# HA_Out.net
KiCad netlist of a schematic drawn in Altium Designer
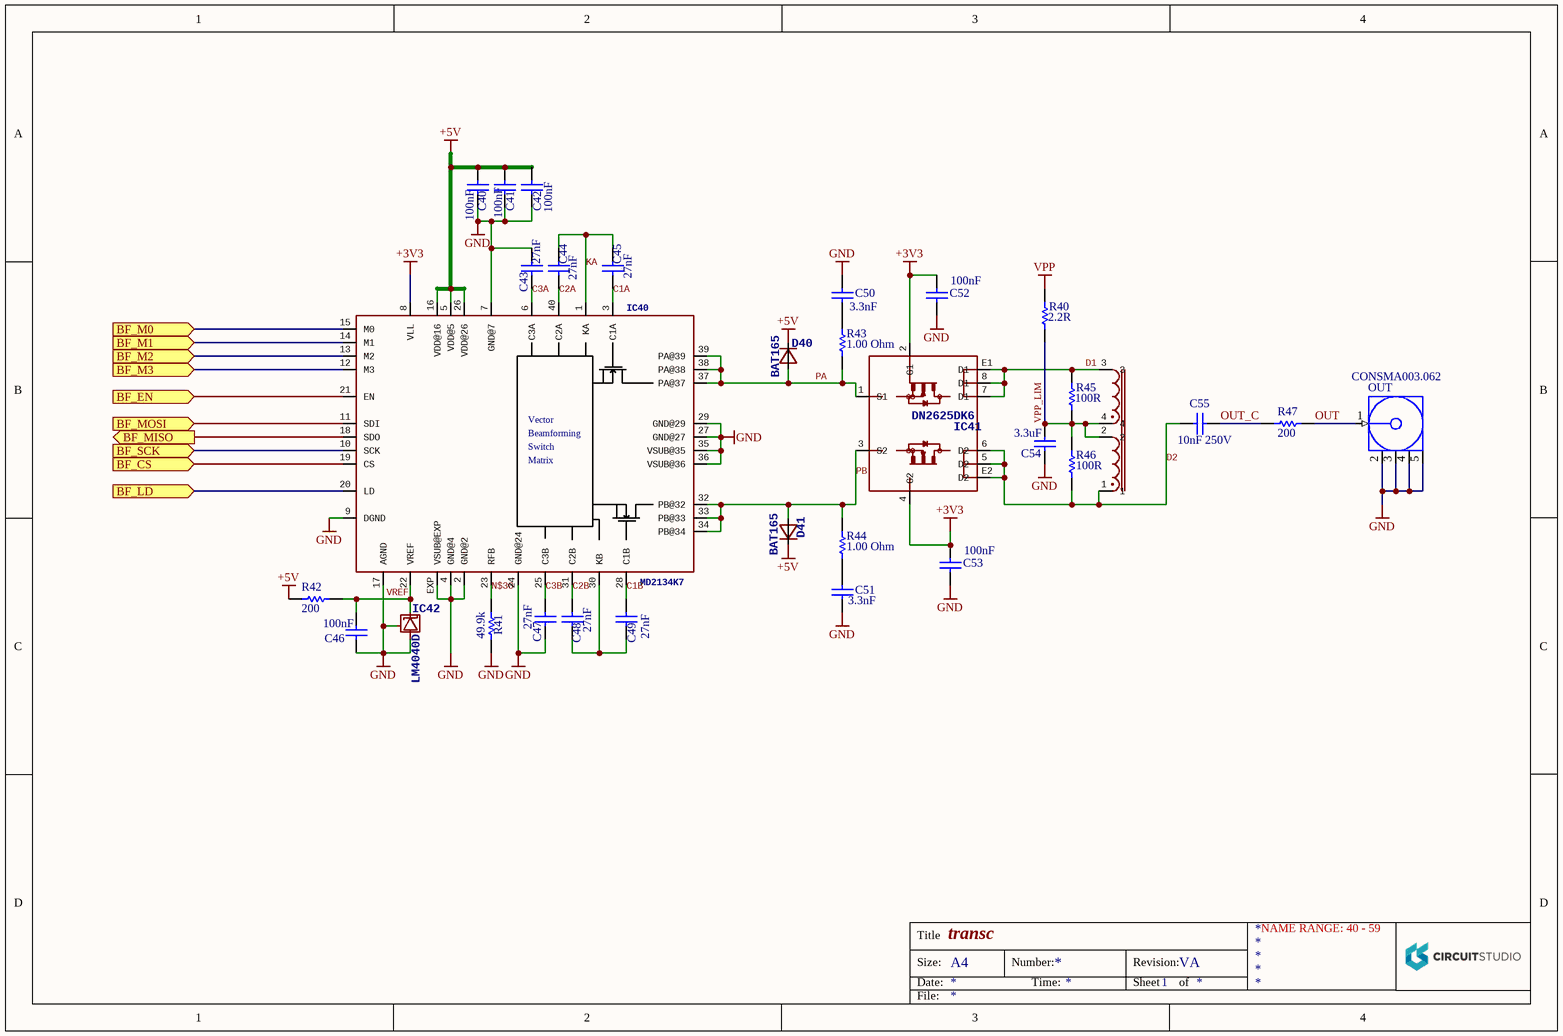
[diagram p0: HA_Out.SchDoc]

(export (version "E")
  (design (tool "Eeschema 10.0.6"))
  (components
    (comp (ref "C40")
      (value "100nF")
      (footprint "CAPC0603(1608)100_L")
      (description "CAP 100nF 100V ±10% 0603 (1608 Metric) Thickness 1mm SMD")
      (fields (field (name "TOLERANCE") "±10%") (field (name "Comment") "100nF 100V"))
      (libsource (lib "Altium Content Vault") (part "CMP-1035-00529-1"))
    )
    (comp (ref "C41")
      (value "100nF")
      (footprint "CAPC0603(1608)100_L")
      (description "CAP 100nF 100V ±10% 0603 (1608 Metric) Thickness 1mm SMD")
      (fields (field (name "TOLERANCE") "±10%") (field (name "Comment") "100nF 100V"))
      (libsource (lib "Altium Content Vault") (part "CMP-1035-00529-1"))
    )
    (comp (ref "C42")
      (value "100nF")
      (footprint "CAPC0603(1608)100_L")
      (description "CAP 100nF 100V ±10% 0603 (1608 Metric) Thickness 1mm SMD")
      (fields (field (name "TOLERANCE") "±10%") (field (name "Comment") "100nF 100V"))
      (libsource (lib "Altium Content Vault") (part "CMP-1035-00529-1"))
    )
    (comp (ref "C43")
      (value "27nF")
      (footprint "CAPC0603(1608)100_L")
      (description "CAP 27nF 100V ±10% 0603 (1608 Metric) Thickness 1mm SMD")
      (fields (field (name "TOLERANCE") "±10%") (field (name "Comment") "27nF 100V"))
      (libsource (lib "Altium Content Vault") (part "CMP-1035-00529-1"))
    )
    (comp (ref "C44")
      (value "27nF")
      (footprint "CAPC0603(1608)100_L")
      (description "CAP 27nF 100V ±10% 0603 (1608 Metric) Thickness 1mm SMD")
      (fields (field (name "TOLERANCE") "±10%") (field (name "Comment") "27nF 100V"))
      (libsource (lib "Altium Content Vault") (part "CMP-1035-00529-1"))
    )
    (comp (ref "C45")
      (value "27nF")
      (footprint "CAPC0603(1608)100_L")
      (description "CAP 27nF 100V ±10% 0603 (1608 Metric) Thickness 1mm SMD")
      (fields (field (name "TOLERANCE") "±10%") (field (name "Comment") "27nF 100V"))
      (libsource (lib "Altium Content Vault") (part "CMP-1035-00529-1"))
    )
    (comp (ref "C46")
      (value "100nF")
      (footprint "CAPC0603(1608)100_L")
      (description "CAP 100nF 100V ±10% 0603 (1608 Metric) Thickness 1mm SMD")
      (fields (field (name "TOLERANCE") "±10%") (field (name "Comment") "100nF 100V"))
      (libsource (lib "Altium Content Vault") (part "CMP-1035-00529-1"))
    )
    (comp (ref "C47")
      (value "27nF")
      (footprint "CAPC0603(1608)100_L")
      (description "CAP 27nF 100V ±10% 0603 (1608 Metric) Thickness 1mm SMD")
      (fields (field (name "TOLERANCE") "±10%") (field (name "Comment") "27nF 100V"))
      (libsource (lib "Altium Content Vault") (part "CMP-1035-00529-1"))
    )
    (comp (ref "C48")
      (value "27nF")
      (footprint "CAPC0603(1608)100_L")
      (description "CAP 27nF 100V ±10% 0603 (1608 Metric) Thickness 1mm SMD")
      (fields (field (name "TOLERANCE") "±10%") (field (name "Comment") "27nF 100V"))
      (libsource (lib "Altium Content Vault") (part "CMP-1035-00529-1"))
    )
    (comp (ref "C49")
      (value "27nF")
      (footprint "CAPC0603(1608)100_L")
      (description "CAP 27nF 100V ±10% 0603 (1608 Metric) Thickness 1mm SMD")
      (fields (field (name "TOLERANCE") "±10%") (field (name "Comment") "27nF 100V"))
      (libsource (lib "Altium Content Vault") (part "CMP-1035-00529-1"))
    )
    (comp (ref "C50")
      (value "3.3nF")
      (footprint "CAPC0805(2012)75_N")
      (description "CAP 3.3nF 100V 0805 (2012 Metric) Thickness 0.75mm SMD")
      (fields (field (name "TOLERANCE") "±10%") (field (name "Comment") "3.3nF 100V"))
      (libsource (lib "Altium Content Vault") (part "CMP-1036-00417-1"))
    )
    (comp (ref "C51")
      (value "3.3nF")
      (footprint "CAPC0805(2012)75_N")
      (description "CAP 3.3nF 100V 0805 (2012 Metric) Thickness 0.75mm SMD")
      (fields (field (name "TOLERANCE") "±10%") (field (name "Comment") "3.3nF 100V"))
      (libsource (lib "Altium Content Vault") (part "CMP-1036-00417-1"))
    )
    (comp (ref "C52")
      (value "100nF")
      (footprint "CAPC0603(1608)100_L")
      (description "CAP 100nF 100V ±10% 0603 (1608 Metric) Thickness 1mm SMD")
      (fields (field (name "TOLERANCE") "±10%") (field (name "Comment") "100nF 100V"))
      (libsource (lib "Altium Content Vault") (part "CMP-1035-00529-1"))
    )
    (comp (ref "C53")
      (value "100nF")
      (footprint "CAPC0603(1608)100_L")
      (description "CAP 100nF 100V ±10% 0603 (1608 Metric) Thickness 1mm SMD")
      (fields (field (name "TOLERANCE") "±10%") (field (name "Comment") "100nF 100V"))
      (libsource (lib "Altium Content Vault") (part "CMP-1035-00529-1"))
    )
    (comp (ref "C54")
      (value "3.3uF")
      (footprint "CAPC1206(3216)190_N")
      (description "CAP 3.3uF 100V ±20% 1206 (3216 Metric) Thickness 1.9mm SMD")
      (fields (field (name "TOLERANCE") "Â±20%") (field (name "Comment") "3.3uF 100V"))
      (libsource (lib "Altium Content Vault") (part "CMP-1037-04411-1"))
    )
    (comp (ref "C55")
      (value "10nF 250V")
      (footprint "CAPC0805(2012)75_N")
      (description "CAP 0805 (2012 Metric) Thickness 0.75mm SMD")
      (fields (field (name "TOLERANCE") "±10%"))
      (libsource (lib "Altium Content Vault") (part "CMP-1036-00417-1"))
    )
    (comp (ref "D40") (value "BAT165") (footprint "SOD323") (libsource (lib "mms") (part "DIODE_SOD323")))
    (comp (ref "D41") (value "BAT165") (footprint "SOD323") (libsource (lib "mms") (part "DIODE_SOD323")))
    (comp (ref "IC40")
      (value "MD2134K7")
      (footprint "QFN40-5X5")
      (libsource (lib "microchip") (part "MD2134K7"))
    )
    (comp (ref "IC41")
      (value "DN2625DK6")
      (footprint "DFN8K6")
      (libsource (lib "microchip") (part "DN2625DK6"))
    )
    (comp (ref "IC42")
      (value "LM4040D")
      (footprint "DBZ_R-PDSO-G3")
      (libsource (lib "mms") (part "LM4040DBZ"))
    )
    (comp (ref "L40")
      (value "LPD6235-682MEB")
      (footprint "LPD5235MR")
      (description "Coilcraft")
      (libsource (lib "coilcraft") (part "LPD5235MR"))
    )
    (comp (ref "OUT")
      (value "CONSMA003.062")
      (footprint "CON-SMA-EDGE062")
      (description "SMA Female Edge Mount Connector")
      (libsource (lib "Linx Technologies Connector") (part "CONSMA003.062"))
    )
    (comp (ref "R40")
      (value "2.2R")
      (footprint "RESC2512(6432)_M")
      (description "1W 5% 2512 (6432 Metric)  SMD")
      (fields (field (name "TOLERANCE") "5 %") (field (name "POWER") "1 W"))
      (libsource (lib "Altium Content Vault") (part "CMP-1018-00050-1"))
    )
    (comp (ref "R41")
      (value "49.9k")
      (footprint "RESC0603(1608)_N")
      (description "49.9k 1% 0603 SMD")
      (fields (field (name "TOLERANCE") "1 %"))
      (libsource (lib "Altium Content Vault") (part "CMP-1012-00122-1"))
    )
    (comp (ref "R42")
      (value "200")
      (footprint "RESC0603(1608)_N")
      (description "200 1% 0603 SMD")
      (fields (field (name "TOLERANCE") "1 %"))
      (libsource (lib "Altium Content Vault") (part "CMP-1012-00122-1"))
    )
    (comp (ref "R43")
      (value "1.00 Ohm")
      (footprint "RESC2512(6432)_M")
      (description "1R 1W 5% 2512 (6432 Metric)  SMD")
      (fields (field (name "TOLERANCE") "5 %") (field (name "POWER") "1 W"))
      (libsource (lib "Altium Content Vault") (part "CMP-1018-00050-1"))
    )
    (comp (ref "R44")
      (value "1.00 Ohm")
      (footprint "RESC2512(6432)_M")
      (description "1R 1W 5% 2512 (6432 Metric)  SMD")
      (fields (field (name "TOLERANCE") "5 %") (field (name "POWER") "1 W"))
      (libsource (lib "Altium Content Vault") (part "CMP-1018-00050-1"))
    )
    (comp (ref "R45")
      (value "100R")
      (footprint "RESC2512(6432)_M")
      (description "100R 1W 5% 2512 (6432 Metric)  SMD")
      (fields (field (name "TOLERANCE") "5 %") (field (name "POWER") "1 W"))
      (libsource (lib "Altium Content Vault") (part "CMP-1018-00050-1"))
    )
    (comp (ref "R46")
      (value "100R")
      (footprint "RESC2512(6432)_M")
      (description "100R 1W 5% 2512 (6432 Metric)  SMD")
      (fields (field (name "TOLERANCE") "5 %") (field (name "POWER") "1 W"))
      (libsource (lib "Altium Content Vault") (part "CMP-1018-00050-1"))
    )
    (comp (ref "R47")
      (value "200")
      (footprint "RESC0805(2012)_L")
      (description "0.125W 1% 0805 (2012 Metric)  SMD")
      (fields (field (name "POWER") "0.125 W") (field (name "TOLERANCE") "1 %"))
      (libsource (lib "Altium Content Vault") (part "CMP-1013-00429-1"))
    )
  )
  (nets
    (net (code "1") (name "+3V3") (class "Default")
      (node (ref "C52") (pin "2") (pinfunction "2_2") (pintype "passive"))
      (node (ref "C53") (pin "2") (pinfunction "2_2") (pintype "passive"))
      (node (ref "IC40") (pin "8") (pinfunction "VLL_8") (pintype "power_in"))
      (node (ref "IC41") (pin "2") (pinfunction "G1_2") (pintype "passive"))
      (node (ref "IC41") (pin "4") (pinfunction "G2_4") (pintype "passive"))
    )
    (net (code "2") (name "+5V") (class "Default")
      (node (ref "C40") (pin "2") (pinfunction "2_2") (pintype "passive"))
      (node (ref "C41") (pin "2") (pinfunction "2_2") (pintype "passive"))
      (node (ref "C42") (pin "2") (pinfunction "2_2") (pintype "passive"))
      (node (ref "D40") (pin "C") (pinfunction "C_C") (pintype "passive"))
      (node (ref "D41") (pin "C") (pinfunction "C_C") (pintype "passive"))
      (node (ref "IC40") (pin "16") (pinfunction "VDD@16_16") (pintype "power_in"))
      (node (ref "IC40") (pin "26") (pinfunction "VDD@26_26") (pintype "power_in"))
      (node (ref "IC40") (pin "5") (pinfunction "VDD@5_5") (pintype "power_in"))
      (node (ref "R42") (pin "2") (pinfunction "2_2") (pintype "passive"))
    )
    (net (code "3") (name "/BF_CS") (class "Default")
      (node (ref "IC40") (pin "19") (pinfunction "CS_19") (pintype "passive"))
    )
    (net (code "4") (name "/BF_EN") (class "Default")
      (node (ref "IC40") (pin "21") (pinfunction "EN_21") (pintype "passive"))
    )
    (net (code "5") (name "/BF_LD") (class "Default")
      (node (ref "IC40") (pin "20") (pinfunction "LD_20") (pintype "passive"))
    )
    (net (code "6") (name "/BF_M0") (class "Default")
      (node (ref "IC40") (pin "15") (pinfunction "M0_15") (pintype "passive"))
    )
    (net (code "7") (name "/BF_M1") (class "Default")
      (node (ref "IC40") (pin "14") (pinfunction "M1_14") (pintype "passive"))
    )
    (net (code "8") (name "/BF_M2") (class "Default")
      (node (ref "IC40") (pin "13") (pinfunction "M2_13") (pintype "passive"))
    )
    (net (code "9") (name "/BF_M3") (class "Default")
      (node (ref "IC40") (pin "12") (pinfunction "M3_12") (pintype "passive"))
    )
    (net (code "10") (name "/BF_MISO") (class "Default")
      (node (ref "IC40") (pin "18") (pinfunction "SDO_18") (pintype "passive"))
    )
    (net (code "11") (name "/BF_MOSI") (class "Default")
      (node (ref "IC40") (pin "11") (pinfunction "SDI_11") (pintype "passive"))
    )
    (net (code "12") (name "/BF_SCK") (class "Default")
      (node (ref "IC40") (pin "10") (pinfunction "SCK_10") (pintype "passive"))
    )
    (net (code "13") (name "/C1A") (class "Default")
      (node (ref "C45") (pin "1") (pinfunction "1_1") (pintype "passive"))
      (node (ref "IC40") (pin "3") (pinfunction "C1A_3") (pintype "passive"))
    )
    (net (code "14") (name "/C1B") (class "Default")
      (node (ref "C49") (pin "2") (pinfunction "2_2") (pintype "passive"))
      (node (ref "IC40") (pin "28") (pinfunction "C1B_28") (pintype "passive"))
    )
    (net (code "15") (name "/C2A") (class "Default")
      (node (ref "C44") (pin "1") (pinfunction "1_1") (pintype "passive"))
      (node (ref "IC40") (pin "40") (pinfunction "C2A_40") (pintype "passive"))
    )
    (net (code "16") (name "/C2B") (class "Default")
      (node (ref "C48") (pin "2") (pinfunction "2_2") (pintype "passive"))
      (node (ref "IC40") (pin "31") (pinfunction "C2B_31") (pintype "passive"))
    )
    (net (code "17") (name "/C3A") (class "Default")
      (node (ref "C43") (pin "1") (pinfunction "1_1") (pintype "passive"))
      (node (ref "IC40") (pin "6") (pinfunction "C3A_6") (pintype "passive"))
    )
    (net (code "18") (name "/C3B") (class "Default")
      (node (ref "C47") (pin "2") (pinfunction "2_2") (pintype "passive"))
      (node (ref "IC40") (pin "25") (pinfunction "C3B_25") (pintype "passive"))
    )
    (net (code "19") (name "/D1") (class "Default")
      (node (ref "IC41") (pin "7") (pinfunction "D1_7") (pintype "passive"))
      (node (ref "IC41") (pin "8") (pinfunction "D1_8") (pintype "passive"))
      (node (ref "IC41") (pin "E1") (pinfunction "D1_E1") (pintype "passive"))
      (node (ref "L40") (pin "3") (pinfunction "3_3") (pintype "passive"))
      (node (ref "R45") (pin "2") (pinfunction "2_2") (pintype "passive"))
    )
    (net (code "20") (name "/D2") (class "Default")
      (node (ref "C55") (pin "2") (pinfunction "2_2") (pintype "passive"))
      (node (ref "IC41") (pin "5") (pinfunction "D2_5") (pintype "passive"))
      (node (ref "IC41") (pin "6") (pinfunction "D2_6") (pintype "passive"))
      (node (ref "IC41") (pin "E2") (pinfunction "D2_E2") (pintype "passive"))
      (node (ref "L40") (pin "1") (pinfunction "1_1") (pintype "passive"))
      (node (ref "R46") (pin "1") (pinfunction "1_1") (pintype "passive"))
    )
    (net (code "21") (name "/KA") (class "Default")
      (node (ref "C44") (pin "2") (pinfunction "2_2") (pintype "passive"))
      (node (ref "C45") (pin "2") (pinfunction "2_2") (pintype "passive"))
      (node (ref "IC40") (pin "1") (pinfunction "KA_1") (pintype "passive"))
    )
    (net (code "22") (name "/N$30") (class "Default")
      (node (ref "IC40") (pin "23") (pinfunction "RFB_23") (pintype "passive"))
      (node (ref "R41") (pin "2") (pinfunction "2_2") (pintype "passive"))
    )
    (net (code "23") (name "/OUT") (class "Default")
      (node (ref "OUT") (pin "1") (pinfunction "Signal_1") (pintype "input"))
      (node (ref "R47") (pin "2") (pinfunction "2_2") (pintype "passive"))
    )
    (net (code "24") (name "/OUT_C") (class "Default")
      (node (ref "C55") (pin "1") (pinfunction "1_1") (pintype "passive"))
      (node (ref "R47") (pin "1") (pinfunction "1_1") (pintype "passive"))
    )
    (net (code "25") (name "/PA") (class "Default")
      (node (ref "D40") (pin "A") (pinfunction "A_A") (pintype "passive"))
      (node (ref "IC40") (pin "37") (pinfunction "PA@37_37") (pintype "passive"))
      (node (ref "IC40") (pin "38") (pinfunction "PA@38_38") (pintype "passive"))
      (node (ref "IC40") (pin "39") (pinfunction "PA@39_39") (pintype "passive"))
      (node (ref "IC41") (pin "1") (pinfunction "S1_1") (pintype "passive"))
      (node (ref "R43") (pin "1") (pinfunction "1_1") (pintype "passive"))
    )
    (net (code "26") (name "/PB") (class "Default")
      (node (ref "D41") (pin "A") (pinfunction "A_A") (pintype "passive"))
      (node (ref "IC40") (pin "32") (pinfunction "PB@32_32") (pintype "passive"))
      (node (ref "IC40") (pin "33") (pinfunction "PB@33_33") (pintype "passive"))
      (node (ref "IC40") (pin "34") (pinfunction "PB@34_34") (pintype "passive"))
      (node (ref "IC41") (pin "3") (pinfunction "S2_3") (pintype "passive"))
      (node (ref "R44") (pin "2") (pinfunction "2_2") (pintype "passive"))
    )
    (net (code "27") (name "/VPP_LIM") (class "Default")
      (node (ref "C54") (pin "2") (pinfunction "2_2") (pintype "passive"))
      (node (ref "L40") (pin "2") (pinfunction "2_2") (pintype "passive"))
      (node (ref "L40") (pin "4") (pinfunction "4_4") (pintype "passive"))
      (node (ref "R40") (pin "1") (pinfunction "1_1") (pintype "passive"))
      (node (ref "R45") (pin "1") (pinfunction "1_1") (pintype "passive"))
      (node (ref "R46") (pin "2") (pinfunction "2_2") (pintype "passive"))
    )
    (net (code "28") (name "/VREF") (class "Default")
      (node (ref "C46") (pin "2") (pinfunction "2_2") (pintype "passive"))
      (node (ref "IC40") (pin "22") (pinfunction "VREF_22") (pintype "power_in"))
      (node (ref "IC42") (pin "1") (pinfunction "C_1") (pintype "passive"))
      (node (ref "R42") (pin "1") (pinfunction "1_1") (pintype "passive"))
    )
    (net (code "29") (name "GND") (class "Default")
      (node (ref "C40") (pin "1") (pinfunction "1_1") (pintype "passive"))
      (node (ref "C41") (pin "1") (pinfunction "1_1") (pintype "passive"))
      (node (ref "C42") (pin "1") (pinfunction "1_1") (pintype "passive"))
      (node (ref "C43") (pin "2") (pinfunction "2_2") (pintype "passive"))
      (node (ref "C46") (pin "1") (pinfunction "1_1") (pintype "passive"))
      (node (ref "C47") (pin "1") (pinfunction "1_1") (pintype "passive"))
      (node (ref "C50") (pin "2") (pinfunction "2_2") (pintype "passive"))
      (node (ref "C51") (pin "1") (pinfunction "1_1") (pintype "passive"))
      (node (ref "C52") (pin "1") (pinfunction "1_1") (pintype "passive"))
      (node (ref "C53") (pin "1") (pinfunction "1_1") (pintype "passive"))
      (node (ref "C54") (pin "1") (pinfunction "1_1") (pintype "passive"))
      (node (ref "IC40") (pin "17") (pinfunction "AGND_17") (pintype "power_in"))
      (node (ref "IC40") (pin "2") (pinfunction "GND@2_2") (pintype "power_in"))
      (node (ref "IC40") (pin "24") (pinfunction "GND@24_24") (pintype "power_in"))
      (node (ref "IC40") (pin "27") (pinfunction "GND@27_27") (pintype "power_in"))
      (node (ref "IC40") (pin "29") (pinfunction "GND@29_29") (pintype "power_in"))
      (node (ref "IC40") (pin "35") (pinfunction "VSUB@35_35") (pintype "power_in"))
      (node (ref "IC40") (pin "36") (pinfunction "VSUB@36_36") (pintype "power_in"))
      (node (ref "IC40") (pin "4") (pinfunction "GND@4_4") (pintype "power_in"))
      (node (ref "IC40") (pin "7") (pinfunction "GND@7_7") (pintype "power_in"))
      (node (ref "IC40") (pin "9") (pinfunction "DGND_9") (pintype "power_in"))
      (node (ref "IC40") (pin "EXP") (pinfunction "VSUB@EXP_EXP") (pintype "power_in"))
      (node (ref "IC42") (pin "2") (pinfunction "A_2") (pintype "passive"))
      (node (ref "IC42") (pin "3") (pinfunction "FB_3") (pintype "passive"))
      (node (ref "OUT") (pin "2") (pinfunction "GND_2") (pintype "power_in"))
      (node (ref "OUT") (pin "3") (pinfunction "GND_3") (pintype "power_in"))
      (node (ref "OUT") (pin "4") (pinfunction "GND_4") (pintype "power_in"))
      (node (ref "OUT") (pin "5") (pinfunction "GND_5") (pintype "power_in"))
      (node (ref "R41") (pin "1") (pinfunction "1_1") (pintype "passive"))
    )
    (net (code "30") (name "Net-(C50-Pad1)") (class "Default")
      (node (ref "C50") (pin "1") (pinfunction "1_1") (pintype "passive"))
      (node (ref "R43") (pin "2") (pinfunction "2_2") (pintype "passive"))
    )
    (net (code "31") (name "Net-(C51-Pad2)") (class "Default")
      (node (ref "C51") (pin "2") (pinfunction "2_2") (pintype "passive"))
      (node (ref "R44") (pin "1") (pinfunction "1_1") (pintype "passive"))
    )
    (net (code "32") (name "Net-(IC40-KB)") (class "Default")
      (node (ref "C48") (pin "1") (pinfunction "1_1") (pintype "passive"))
      (node (ref "C49") (pin "1") (pinfunction "1_1") (pintype "passive"))
      (node (ref "IC40") (pin "30") (pinfunction "KB_30") (pintype "passive"))
    )
    (net (code "33") (name "VPP") (class "Default")
      (node (ref "R40") (pin "2") (pinfunction "2_2") (pintype "passive"))
    )
  )
)
